# gpio.net
KiCad netlist of a schematic drawn in Altium Designer
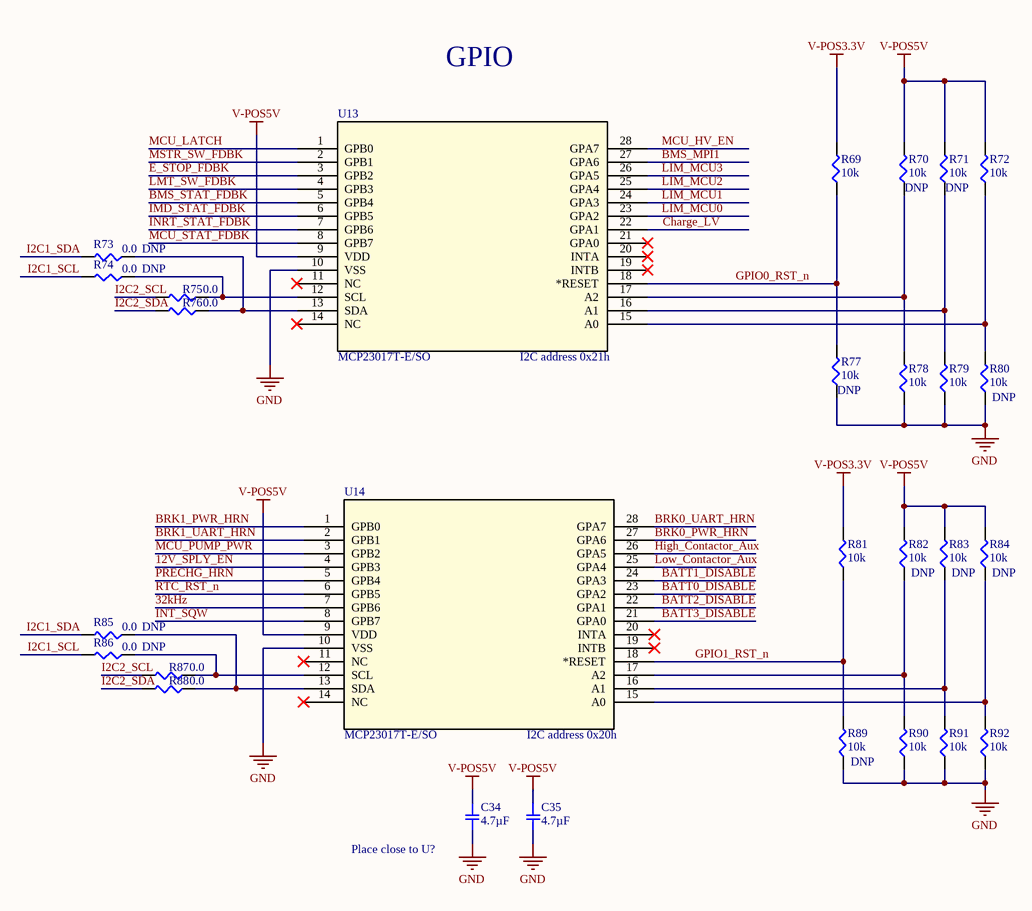
[diagram p0: gpio.SchDoc]

(export (version "E")
  (design (tool "Eeschema 10.0.6"))
  (components
    (comp (ref "C34")
      (value "4.7µF")
      (footprint "SMD-0805C")
      (description "CAP CER 4.7UF 6.3V X5R 0805")
      (fields
        (field (name "DIGI-KEY PART NUMBER") "490-9749-1-ND")
        (field (name "PART NUMBER") "GRM21BR60J475KA11L")
      )
      (libsource (lib "capacitor") (part "GRM21BR60J475KA11L"))
    )
    (comp (ref "C35")
      (value "4.7µF")
      (footprint "SMD-0805C")
      (description "CAP CER 4.7UF 6.3V X5R 0805")
      (fields
        (field (name "DIGI-KEY PART NUMBER") "490-9749-1-ND")
        (field (name "PART NUMBER") "GRM21BR60J475KA11L")
      )
      (libsource (lib "capacitor") (part "GRM21BR60J475KA11L"))
    )
    (comp (ref "R69")
      (value "10k")
      (footprint "SMD-0805-RES")
      (description "RES SMD 10K OHM 5% 1/2W 0805")
      (fields (field (name "PART NUMBER") "ERJ-P06J103V") (field (name "DIGI-KEY PART NUMBER") "P10KADCT-ND"))
      (libsource (lib "resistors") (part "ERJ-P06J103V"))
    )
    (comp (ref "R70")
      (value "10k")
      (footprint "SMD-0805-RES")
      (description "RES SMD 10K OHM 5% 1/2W 0805")
      (fields
        (field (name "PART NUMBER") "ERJ-P06J103V")
        (field (name "DIGI-KEY PART NUMBER") "P10KADCT-ND")
        (field (name "DNP") "DNP")
      )
      (libsource (lib "resistors") (part "ERJ-P06J103V"))
    )
    (comp (ref "R71")
      (value "10k")
      (footprint "SMD-0805-RES")
      (description "RES SMD 10K OHM 5% 1/2W 0805")
      (fields
        (field (name "PART NUMBER") "ERJ-P06J103V")
        (field (name "DIGI-KEY PART NUMBER") "P10KADCT-ND")
        (field (name "DNP") "DNP")
      )
      (libsource (lib "resistors") (part "ERJ-P06J103V"))
    )
    (comp (ref "R72")
      (value "10k")
      (footprint "SMD-0805-RES")
      (description "RES SMD 10K OHM 5% 1/2W 0805")
      (fields (field (name "PART NUMBER") "ERJ-P06J103V") (field (name "DIGI-KEY PART NUMBER") "P10KADCT-ND"))
      (libsource (lib "resistors") (part "ERJ-P06J103V"))
    )
    (comp (ref "R73")
      (value "0.0")
      (footprint "SMD-0805-RES")
      (description "RES SMD 0.0 OHM JUMPER 1/8W 0805")
      (fields
        (field (name "PART NUMBER") "ERJ-6GEY0R00V")
        (field (name "DIGI-KEY PART NUMBER") "P0.0ACT-ND")
        (field (name "DNP") "DNP")
      )
      (libsource (lib "resistors") (part "ERJ-6GEY0R00V"))
    )
    (comp (ref "R74")
      (value "0.0")
      (footprint "SMD-0805-RES")
      (description "RES SMD 0.0 OHM JUMPER 1/8W 0805")
      (fields
        (field (name "PART NUMBER") "ERJ-6GEY0R00V")
        (field (name "DIGI-KEY PART NUMBER") "P0.0ACT-ND")
        (field (name "DNP") "DNP")
      )
      (libsource (lib "resistors") (part "ERJ-6GEY0R00V"))
    )
    (comp (ref "R75")
      (value "0.0")
      (footprint "SMD-0805-RES")
      (description "RES SMD 0.0 OHM JUMPER 1/8W 0805")
      (fields (field (name "PART NUMBER") "ERJ-6GEY0R00V") (field (name "DIGI-KEY PART NUMBER") "P0.0ACT-ND"))
      (libsource (lib "resistors") (part "ERJ-6GEY0R00V"))
    )
    (comp (ref "R76")
      (value "0.0")
      (footprint "SMD-0805-RES")
      (description "RES SMD 0.0 OHM JUMPER 1/8W 0805")
      (fields (field (name "PART NUMBER") "ERJ-6GEY0R00V") (field (name "DIGI-KEY PART NUMBER") "P0.0ACT-ND"))
      (libsource (lib "resistors") (part "ERJ-6GEY0R00V"))
    )
    (comp (ref "R77")
      (value "10k")
      (footprint "SMD-0805-RES")
      (description "RES SMD 10K OHM 5% 1/2W 0805")
      (fields
        (field (name "PART NUMBER") "ERJ-P06J103V")
        (field (name "DIGI-KEY PART NUMBER") "P10KADCT-ND")
        (field (name "DNP") "DNP")
      )
      (libsource (lib "resistors") (part "ERJ-P06J103V"))
    )
    (comp (ref "R78")
      (value "10k")
      (footprint "SMD-0805-RES")
      (description "RES SMD 10K OHM 5% 1/2W 0805")
      (fields (field (name "PART NUMBER") "ERJ-P06J103V") (field (name "DIGI-KEY PART NUMBER") "P10KADCT-ND"))
      (libsource (lib "resistors") (part "ERJ-P06J103V"))
    )
    (comp (ref "R79")
      (value "10k")
      (footprint "SMD-0805-RES")
      (description "RES SMD 10K OHM 5% 1/2W 0805")
      (fields (field (name "PART NUMBER") "ERJ-P06J103V") (field (name "DIGI-KEY PART NUMBER") "P10KADCT-ND"))
      (libsource (lib "resistors") (part "ERJ-P06J103V"))
    )
    (comp (ref "R80")
      (value "10k")
      (footprint "SMD-0805-RES")
      (description "RES SMD 10K OHM 5% 1/2W 0805")
      (fields
        (field (name "PART NUMBER") "ERJ-P06J103V")
        (field (name "DIGI-KEY PART NUMBER") "P10KADCT-ND")
        (field (name "DNP") "DNP")
      )
      (libsource (lib "resistors") (part "ERJ-P06J103V"))
    )
    (comp (ref "R81")
      (value "10k")
      (footprint "SMD-0805-RES")
      (description "RES SMD 10K OHM 5% 1/2W 0805")
      (fields (field (name "PART NUMBER") "ERJ-P06J103V") (field (name "DIGI-KEY PART NUMBER") "P10KADCT-ND"))
      (libsource (lib "resistors") (part "ERJ-P06J103V"))
    )
    (comp (ref "R82")
      (value "10k")
      (footprint "SMD-0805-RES")
      (description "RES SMD 10K OHM 5% 1/2W 0805")
      (fields
        (field (name "PART NUMBER") "ERJ-P06J103V")
        (field (name "DIGI-KEY PART NUMBER") "P10KADCT-ND")
        (field (name "DNP") "DNP")
      )
      (libsource (lib "resistors") (part "ERJ-P06J103V"))
    )
    (comp (ref "R83")
      (value "10k")
      (footprint "SMD-0805-RES")
      (description "RES SMD 10K OHM 5% 1/2W 0805")
      (fields
        (field (name "PART NUMBER") "ERJ-P06J103V")
        (field (name "DIGI-KEY PART NUMBER") "P10KADCT-ND")
        (field (name "DNP") "DNP")
      )
      (libsource (lib "resistors") (part "ERJ-P06J103V"))
    )
    (comp (ref "R84")
      (value "10k")
      (footprint "SMD-0805-RES")
      (description "RES SMD 10K OHM 5% 1/2W 0805")
      (fields
        (field (name "PART NUMBER") "ERJ-P06J103V")
        (field (name "DIGI-KEY PART NUMBER") "P10KADCT-ND")
        (field (name "DNP") "DNP")
      )
      (libsource (lib "resistors") (part "ERJ-P06J103V"))
    )
    (comp (ref "R85")
      (value "0.0")
      (footprint "SMD-0805-RES")
      (description "RES SMD 0.0 OHM JUMPER 1/8W 0805")
      (fields
        (field (name "PART NUMBER") "ERJ-6GEY0R00V")
        (field (name "DIGI-KEY PART NUMBER") "P0.0ACT-ND")
        (field (name "DNP") "DNP")
      )
      (libsource (lib "resistors") (part "ERJ-6GEY0R00V"))
    )
    (comp (ref "R86")
      (value "0.0")
      (footprint "SMD-0805-RES")
      (description "RES SMD 0.0 OHM JUMPER 1/8W 0805")
      (fields
        (field (name "PART NUMBER") "ERJ-6GEY0R00V")
        (field (name "DIGI-KEY PART NUMBER") "P0.0ACT-ND")
        (field (name "DNP") "DNP")
      )
      (libsource (lib "resistors") (part "ERJ-6GEY0R00V"))
    )
    (comp (ref "R87")
      (value "0.0")
      (footprint "SMD-0805-RES")
      (description "RES SMD 0.0 OHM JUMPER 1/8W 0805")
      (fields (field (name "PART NUMBER") "ERJ-6GEY0R00V") (field (name "DIGI-KEY PART NUMBER") "P0.0ACT-ND"))
      (libsource (lib "resistors") (part "ERJ-6GEY0R00V"))
    )
    (comp (ref "R88")
      (value "0.0")
      (footprint "SMD-0805-RES")
      (description "RES SMD 0.0 OHM JUMPER 1/8W 0805")
      (fields (field (name "PART NUMBER") "ERJ-6GEY0R00V") (field (name "DIGI-KEY PART NUMBER") "P0.0ACT-ND"))
      (libsource (lib "resistors") (part "ERJ-6GEY0R00V"))
    )
    (comp (ref "R89")
      (value "10k")
      (footprint "SMD-0805-RES")
      (description "RES SMD 10K OHM 5% 1/2W 0805")
      (fields
        (field (name "PART NUMBER") "ERJ-P06J103V")
        (field (name "DIGI-KEY PART NUMBER") "P10KADCT-ND")
        (field (name "DNP") "DNP")
      )
      (libsource (lib "resistors") (part "ERJ-P06J103V"))
    )
    (comp (ref "R90")
      (value "10k")
      (footprint "SMD-0805-RES")
      (description "RES SMD 10K OHM 5% 1/2W 0805")
      (fields (field (name "PART NUMBER") "ERJ-P06J103V") (field (name "DIGI-KEY PART NUMBER") "P10KADCT-ND"))
      (libsource (lib "resistors") (part "ERJ-P06J103V"))
    )
    (comp (ref "R91")
      (value "10k")
      (footprint "SMD-0805-RES")
      (description "RES SMD 10K OHM 5% 1/2W 0805")
      (fields (field (name "PART NUMBER") "ERJ-P06J103V") (field (name "DIGI-KEY PART NUMBER") "P10KADCT-ND"))
      (libsource (lib "resistors") (part "ERJ-P06J103V"))
    )
    (comp (ref "R92")
      (value "10k")
      (footprint "SMD-0805-RES")
      (description "RES SMD 10K OHM 5% 1/2W 0805")
      (fields (field (name "PART NUMBER") "ERJ-P06J103V") (field (name "DIGI-KEY PART NUMBER") "P10KADCT-ND"))
      (libsource (lib "resistors") (part "ERJ-P06J103V"))
    )
    (comp (ref "U13")
      (value "MCP23017T-E/SO")
      (footprint "SOIC28-W_MC-M")
      (description "IC I/O EXPANDER I2C 16B 28SOIC")
      (fields (field (name "MANUFACTURER") "Microchip"))
      (libsource (lib "ic") (part "MCP23017T-E/SO"))
    )
    (comp (ref "U14")
      (value "MCP23017T-E/SO")
      (footprint "SOIC28-W_MC-M")
      (description "IC I/O EXPANDER I2C 16B 28SOIC")
      (fields (field (name "MANUFACTURER") "Microchip"))
      (libsource (lib "ic") (part "MCP23017T-E/SO"))
    )
  )
  (nets
    (net (code "1") (name "/12V_SPLY_EN") (class "Default")
      (node (ref "U14") (pin "4") (pinfunction "GPB3_4") (pintype "passive"))
    )
    (net (code "2") (name "/32kHz") (class "Default")
      (node (ref "U14") (pin "7") (pinfunction "GPB6_7") (pintype "passive"))
    )
    (net (code "3") (name "/BATT0_DISABLE") (class "Default")
      (node (ref "U14") (pin "23") (pinfunction "GPA2_23") (pintype "passive"))
    )
    (net (code "4") (name "/BATT1_DISABLE") (class "Default")
      (node (ref "U14") (pin "24") (pinfunction "GPA3_24") (pintype "passive"))
    )
    (net (code "5") (name "/BATT2_DISABLE") (class "Default")
      (node (ref "U14") (pin "22") (pinfunction "GPA1_22") (pintype "passive"))
    )
    (net (code "6") (name "/BATT3_DISABLE") (class "Default")
      (node (ref "U14") (pin "21") (pinfunction "GPA0_21") (pintype "passive"))
    )
    (net (code "7") (name "/BMS_MPI1") (class "Default")
      (node (ref "U13") (pin "27") (pinfunction "GPA6_27") (pintype "passive"))
    )
    (net (code "8") (name "/BMS_STAT_FDBK") (class "Default")
      (node (ref "U13") (pin "5") (pinfunction "GPB4_5") (pintype "passive"))
    )
    (net (code "9") (name "/BRK0_PWR_HRN") (class "Default")
      (node (ref "U14") (pin "27") (pinfunction "GPA6_27") (pintype "passive"))
    )
    (net (code "10") (name "/BRK0_UART_HRN") (class "Default")
      (node (ref "U14") (pin "28") (pinfunction "GPA7_28") (pintype "passive"))
    )
    (net (code "11") (name "/BRK1_PWR_HRN") (class "Default")
      (node (ref "U14") (pin "1") (pinfunction "GPB0_1") (pintype "passive"))
    )
    (net (code "12") (name "/BRK1_UART_HRN") (class "Default")
      (node (ref "U14") (pin "2") (pinfunction "GPB1_2") (pintype "passive"))
    )
    (net (code "13") (name "/Charge_LV") (class "Default")
      (node (ref "U13") (pin "22") (pinfunction "GPA1_22") (pintype "passive"))
    )
    (net (code "14") (name "/E_STOP_FDBK") (class "Default")
      (node (ref "U13") (pin "3") (pinfunction "GPB2_3") (pintype "passive"))
    )
    (net (code "15") (name "/GPIO0_RST_n") (class "Default")
      (node (ref "R69") (pin "1") (pinfunction "1_1") (pintype "passive"))
      (node (ref "R77") (pin "2") (pinfunction "2_2") (pintype "passive"))
      (node (ref "U13") (pin "18") (pinfunction "*RESET_18") (pintype "passive"))
    )
    (net (code "16") (name "/GPIO1_RST_n") (class "Default")
      (node (ref "R81") (pin "1") (pinfunction "1_1") (pintype "passive"))
      (node (ref "R89") (pin "2") (pinfunction "2_2") (pintype "passive"))
      (node (ref "U14") (pin "18") (pinfunction "*RESET_18") (pintype "passive"))
    )
    (net (code "17") (name "/High_Contactor_Aux") (class "Default")
      (node (ref "U14") (pin "26") (pinfunction "GPA5_26") (pintype "passive"))
    )
    (net (code "18") (name "/I2C1_SCL") (class "Default")
      (node (ref "R74") (pin "2") (pinfunction "2_2") (pintype "passive"))
      (node (ref "R86") (pin "2") (pinfunction "2_2") (pintype "passive"))
    )
    (net (code "19") (name "/I2C1_SDA") (class "Default")
      (node (ref "R73") (pin "2") (pinfunction "2_2") (pintype "passive"))
      (node (ref "R85") (pin "2") (pinfunction "2_2") (pintype "passive"))
    )
    (net (code "20") (name "/I2C2_SCL") (class "Default")
      (node (ref "R75") (pin "2") (pinfunction "2_2") (pintype "passive"))
      (node (ref "R87") (pin "2") (pinfunction "2_2") (pintype "passive"))
    )
    (net (code "21") (name "/I2C2_SDA") (class "Default")
      (node (ref "R76") (pin "2") (pinfunction "2_2") (pintype "passive"))
      (node (ref "R88") (pin "2") (pinfunction "2_2") (pintype "passive"))
    )
    (net (code "22") (name "/IMD_STAT_FDBK") (class "Default")
      (node (ref "U13") (pin "6") (pinfunction "GPB5_6") (pintype "passive"))
    )
    (net (code "23") (name "/INRT_STAT_FDBK") (class "Default")
      (node (ref "U13") (pin "7") (pinfunction "GPB6_7") (pintype "passive"))
    )
    (net (code "24") (name "/INT_SQW") (class "Default")
      (node (ref "U14") (pin "8") (pinfunction "GPB7_8") (pintype "passive"))
    )
    (net (code "25") (name "/LIM_MCU0") (class "Default")
      (node (ref "U13") (pin "23") (pinfunction "GPA2_23") (pintype "passive"))
    )
    (net (code "26") (name "/LIM_MCU1") (class "Default")
      (node (ref "U13") (pin "24") (pinfunction "GPA3_24") (pintype "passive"))
    )
    (net (code "27") (name "/LIM_MCU2") (class "Default")
      (node (ref "U13") (pin "25") (pinfunction "GPA4_25") (pintype "passive"))
    )
    (net (code "28") (name "/LIM_MCU3") (class "Default")
      (node (ref "U13") (pin "26") (pinfunction "GPA5_26") (pintype "passive"))
    )
    (net (code "29") (name "/LMT_SW_FDBK") (class "Default")
      (node (ref "U13") (pin "4") (pinfunction "GPB3_4") (pintype "passive"))
    )
    (net (code "30") (name "/Low_Contactor_Aux") (class "Default")
      (node (ref "U14") (pin "25") (pinfunction "GPA4_25") (pintype "passive"))
    )
    (net (code "31") (name "/MCU_HV_EN") (class "Default")
      (node (ref "U13") (pin "28") (pinfunction "GPA7_28") (pintype "passive"))
    )
    (net (code "32") (name "/MCU_LATCH") (class "Default")
      (node (ref "U13") (pin "1") (pinfunction "GPB0_1") (pintype "passive"))
    )
    (net (code "33") (name "/MCU_PUMP_PWR") (class "Default")
      (node (ref "U14") (pin "3") (pinfunction "GPB2_3") (pintype "passive"))
    )
    (net (code "34") (name "/MCU_STAT_FDBK") (class "Default")
      (node (ref "U13") (pin "8") (pinfunction "GPB7_8") (pintype "passive"))
    )
    (net (code "35") (name "/MSTR_SW_FDBK") (class "Default")
      (node (ref "U13") (pin "2") (pinfunction "GPB1_2") (pintype "passive"))
    )
    (net (code "36") (name "/PRECHG_HRN") (class "Default")
      (node (ref "U14") (pin "5") (pinfunction "GPB4_5") (pintype "passive"))
    )
    (net (code "37") (name "/RTC_RST_n") (class "Default")
      (node (ref "U14") (pin "6") (pinfunction "GPB5_6") (pintype "passive"))
    )
    (net (code "38") (name "GND") (class "Default")
      (node (ref "C34") (pin "2") (pinfunction "2_2") (pintype "passive"))
      (node (ref "C35") (pin "2") (pinfunction "2_2") (pintype "passive"))
      (node (ref "R77") (pin "1") (pinfunction "1_1") (pintype "passive"))
      (node (ref "R78") (pin "1") (pinfunction "1_1") (pintype "passive"))
      (node (ref "R79") (pin "1") (pinfunction "1_1") (pintype "passive"))
      (node (ref "R80") (pin "1") (pinfunction "1_1") (pintype "passive"))
      (node (ref "R89") (pin "1") (pinfunction "1_1") (pintype "passive"))
      (node (ref "R90") (pin "1") (pinfunction "1_1") (pintype "passive"))
      (node (ref "R91") (pin "1") (pinfunction "1_1") (pintype "passive"))
      (node (ref "R92") (pin "1") (pinfunction "1_1") (pintype "passive"))
      (node (ref "U13") (pin "10") (pinfunction "VSS_10") (pintype "passive"))
      (node (ref "U14") (pin "10") (pinfunction "VSS_10") (pintype "passive"))
    )
    (net (code "39") (name "Net-(U13-A0)") (class "Default")
      (node (ref "R72") (pin "1") (pinfunction "1_1") (pintype "passive"))
      (node (ref "R80") (pin "2") (pinfunction "2_2") (pintype "passive"))
      (node (ref "U13") (pin "15") (pinfunction "A0_15") (pintype "passive"))
    )
    (net (code "40") (name "Net-(U13-A1)") (class "Default")
      (node (ref "R71") (pin "1") (pinfunction "1_1") (pintype "passive"))
      (node (ref "R79") (pin "2") (pinfunction "2_2") (pintype "passive"))
      (node (ref "U13") (pin "16") (pinfunction "A1_16") (pintype "passive"))
    )
    (net (code "41") (name "Net-(U13-A2)") (class "Default")
      (node (ref "R70") (pin "1") (pinfunction "1_1") (pintype "passive"))
      (node (ref "R78") (pin "2") (pinfunction "2_2") (pintype "passive"))
      (node (ref "U13") (pin "17") (pinfunction "A2_17") (pintype "passive"))
    )
    (net (code "42") (name "Net-(U13-SCL)") (class "Default")
      (node (ref "R74") (pin "1") (pinfunction "1_1") (pintype "passive"))
      (node (ref "R75") (pin "1") (pinfunction "1_1") (pintype "passive"))
      (node (ref "U13") (pin "12") (pinfunction "SCL_12") (pintype "passive"))
    )
    (net (code "43") (name "Net-(U13-SDA)") (class "Default")
      (node (ref "R73") (pin "1") (pinfunction "1_1") (pintype "passive"))
      (node (ref "R76") (pin "1") (pinfunction "1_1") (pintype "passive"))
      (node (ref "U13") (pin "13") (pinfunction "SDA_13") (pintype "passive"))
    )
    (net (code "44") (name "Net-(U14-A0)") (class "Default")
      (node (ref "R84") (pin "1") (pinfunction "1_1") (pintype "passive"))
      (node (ref "R92") (pin "2") (pinfunction "2_2") (pintype "passive"))
      (node (ref "U14") (pin "15") (pinfunction "A0_15") (pintype "passive"))
    )
    (net (code "45") (name "Net-(U14-A1)") (class "Default")
      (node (ref "R83") (pin "1") (pinfunction "1_1") (pintype "passive"))
      (node (ref "R91") (pin "2") (pinfunction "2_2") (pintype "passive"))
      (node (ref "U14") (pin "16") (pinfunction "A1_16") (pintype "passive"))
    )
    (net (code "46") (name "Net-(U14-A2)") (class "Default")
      (node (ref "R82") (pin "1") (pinfunction "1_1") (pintype "passive"))
      (node (ref "R90") (pin "2") (pinfunction "2_2") (pintype "passive"))
      (node (ref "U14") (pin "17") (pinfunction "A2_17") (pintype "passive"))
    )
    (net (code "47") (name "Net-(U14-SCL)") (class "Default")
      (node (ref "R86") (pin "1") (pinfunction "1_1") (pintype "passive"))
      (node (ref "R87") (pin "1") (pinfunction "1_1") (pintype "passive"))
      (node (ref "U14") (pin "12") (pinfunction "SCL_12") (pintype "passive"))
    )
    (net (code "48") (name "Net-(U14-SDA)") (class "Default")
      (node (ref "R85") (pin "1") (pinfunction "1_1") (pintype "passive"))
      (node (ref "R88") (pin "1") (pinfunction "1_1") (pintype "passive"))
      (node (ref "U14") (pin "13") (pinfunction "SDA_13") (pintype "passive"))
    )
    (net (code "49") (name "V-POS3.3V") (class "Default")
      (node (ref "R69") (pin "2") (pinfunction "2_2") (pintype "passive"))
      (node (ref "R81") (pin "2") (pinfunction "2_2") (pintype "passive"))
    )
    (net (code "50") (name "V-POS5V") (class "Default")
      (node (ref "C34") (pin "1") (pinfunction "1_1") (pintype "passive"))
      (node (ref "C35") (pin "1") (pinfunction "1_1") (pintype "passive"))
      (node (ref "R70") (pin "2") (pinfunction "2_2") (pintype "passive"))
      (node (ref "R71") (pin "2") (pinfunction "2_2") (pintype "passive"))
      (node (ref "R72") (pin "2") (pinfunction "2_2") (pintype "passive"))
      (node (ref "R82") (pin "2") (pinfunction "2_2") (pintype "passive"))
      (node (ref "R83") (pin "2") (pinfunction "2_2") (pintype "passive"))
      (node (ref "R84") (pin "2") (pinfunction "2_2") (pintype "passive"))
      (node (ref "U13") (pin "9") (pinfunction "VDD_9") (pintype "passive"))
      (node (ref "U14") (pin "9") (pinfunction "VDD_9") (pintype "passive"))
    )
    (net (code "51") (name "unconnected-(U13-GPA0-Pad21)") (class "Default")
      (node (ref "U13") (pin "21") (pinfunction "GPA0_21") (pintype "passive+no_connect"))
    )
    (net (code "52") (name "unconnected-(U13-INTA-Pad20)") (class "Default")
      (node (ref "U13") (pin "20") (pinfunction "INTA_20") (pintype "passive+no_connect"))
    )
    (net (code "53") (name "unconnected-(U13-INTB-Pad19)") (class "Default")
      (node (ref "U13") (pin "19") (pinfunction "INTB_19") (pintype "passive+no_connect"))
    )
    (net (code "54") (name "unconnected-(U13-NC-Pad11)") (class "Default")
      (node (ref "U13") (pin "11") (pinfunction "NC_11") (pintype "passive+no_connect"))
    )
    (net (code "55") (name "unconnected-(U13-NC-Pad14)") (class "Default")
      (node (ref "U13") (pin "14") (pinfunction "NC_14") (pintype "passive+no_connect"))
    )
    (net (code "56") (name "unconnected-(U14-INTA-Pad20)") (class "Default")
      (node (ref "U14") (pin "20") (pinfunction "INTA_20") (pintype "passive+no_connect"))
    )
    (net (code "57") (name "unconnected-(U14-INTB-Pad19)") (class "Default")
      (node (ref "U14") (pin "19") (pinfunction "INTB_19") (pintype "passive+no_connect"))
    )
    (net (code "58") (name "unconnected-(U14-NC-Pad11)") (class "Default")
      (node (ref "U14") (pin "11") (pinfunction "NC_11") (pintype "passive+no_connect"))
    )
    (net (code "59") (name "unconnected-(U14-NC-Pad14)") (class "Default")
      (node (ref "U14") (pin "14") (pinfunction "NC_14") (pintype "passive+no_connect"))
    )
  )
)
